# ButtonDaughter.net
KiCad netlist of a schematic drawn in Altium Designer
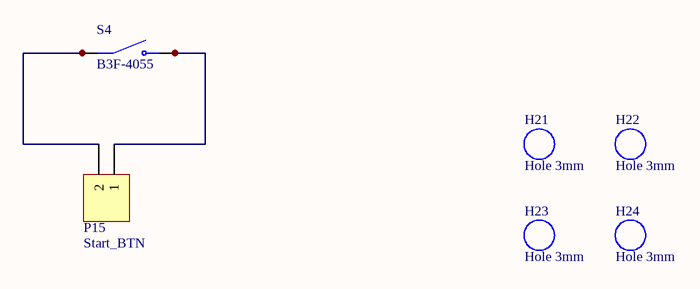
[diagram p0: ButtonDaughter.SchDoc]

(export (version "E")
  (design (tool "Eeschema 10.0.6"))
  (components
    (comp (ref "H21")
      (value "Hole 3mm")
      (footprint "Hole 3mm")
      (libsource (lib "ECE Lib 22") (part "Hole 3mm"))
    )
    (comp (ref "H22")
      (value "Hole 3mm")
      (footprint "Hole 3mm")
      (libsource (lib "ECE Lib 22") (part "Hole 3mm"))
    )
    (comp (ref "H23")
      (value "Hole 3mm")
      (footprint "Hole 3mm")
      (libsource (lib "ECE Lib 22") (part "Hole 3mm"))
    )
    (comp (ref "H24")
      (value "Hole 3mm")
      (footprint "Hole 3mm")
      (libsource (lib "ECE Lib 22") (part "Hole 3mm"))
    )
    (comp (ref "P15")
      (value "Start_BTN")
      (footprint "HDR1X2")
      (description "Header, 2-Pin, Right Angle")
      (fields (field (name "PUBLISHER") "Altium Limited"))
      (libsource (lib "Miscellaneous Connectors") (part "Header 2H"))
    )
    (comp (ref "S4")
      (value "B3F-4055")
      (footprint "SW_B3F-4055")
      (libsource (lib "B3F-4055") (part "B3F-4055"))
    )
  )
  (nets
    (net (code "1") (name "Net-(P15-Pad1)") (class "Default")
      (node (ref "P15") (pin "1") (pinfunction "1_1") (pintype "passive"))
      (node (ref "S4") (pin "3") (pinfunction "NO_3") (pintype "passive"))
      (node (ref "S4") (pin "4") (pinfunction "NO_4") (pintype "passive"))
    )
    (net (code "2") (name "Net-(P15-Pad2)") (class "Default")
      (node (ref "P15") (pin "2") (pinfunction "2_2") (pintype "passive"))
      (node (ref "S4") (pin "1") (pinfunction "COM_1") (pintype "passive"))
      (node (ref "S4") (pin "2") (pinfunction "COM_2") (pintype "passive"))
    )
  )
)
